# Start_Line.net
KiCad netlist of a schematic drawn in EAGLE
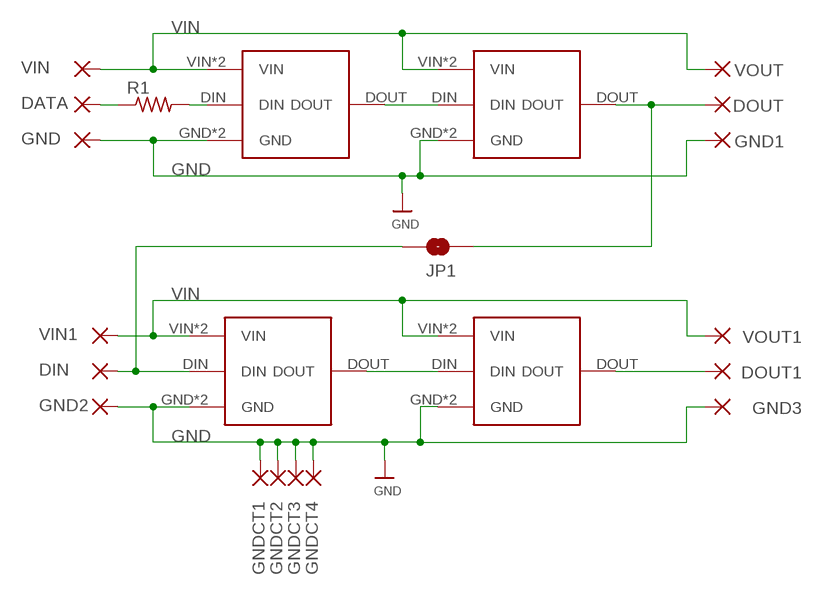
[diagram p0: schematic, sheet 1]

(export (version "E")
  (design (tool "Eeschema 10.0.6"))
  (components
    (comp (ref "DATA")
      (value "SMD5")
      (footprint "eagle-import:SMD2,54-5,08")
      (libsource (lib "eagle-import") (part "wirepad_412_SMD5"))
    )
    (comp (ref "DIN")
      (value "SMD5")
      (footprint "eagle-import:SMD2,54-5,08")
      (libsource (lib "eagle-import") (part "wirepad_412_SMD5"))
    )
    (comp (ref "DOUT")
      (value "SMD5")
      (footprint "eagle-import:SMD2,54-5,08")
      (libsource (lib "eagle-import") (part "wirepad_412_SMD5"))
    )
    (comp (ref "DOUT1")
      (value "SMD5")
      (footprint "eagle-import:SMD2,54-5,08")
      (libsource (lib "eagle-import") (part "wirepad_412_SMD5"))
    )
    (comp (ref "GND")
      (value "SMD5")
      (footprint "eagle-import:SMD2,54-5,08")
      (libsource (lib "eagle-import") (part "wirepad_412_SMD5"))
    )
    (comp (ref "GND1")
      (value "SMD5")
      (footprint "eagle-import:SMD2,54-5,08")
      (libsource (lib "eagle-import") (part "wirepad_412_SMD5"))
    )
    (comp (ref "GND2")
      (value "SMD5")
      (footprint "eagle-import:SMD2,54-5,08")
      (libsource (lib "eagle-import") (part "wirepad_412_SMD5"))
    )
    (comp (ref "GND3")
      (value "SMD5")
      (footprint "eagle-import:SMD2,54-5,08")
      (libsource (lib "eagle-import") (part "wirepad_412_SMD5"))
    )
    (comp (ref "GNDCT1")
      (value "SMD5")
      (footprint "eagle-import:SMD5,5X5")
      (libsource (lib "eagle-import") (part "SMD5"))
    )
    (comp (ref "GNDCT2")
      (value "SMD5")
      (footprint "eagle-import:SMD5,5X5")
      (libsource (lib "eagle-import") (part "SMD5"))
    )
    (comp (ref "GNDCT3")
      (value "SMD5")
      (footprint "eagle-import:SMD5,5X5")
      (libsource (lib "eagle-import") (part "SMD5"))
    )
    (comp (ref "GNDCT4")
      (value "SMD5")
      (footprint "eagle-import:SMD5,5X5")
      (libsource (lib "eagle-import") (part "SMD5"))
    )
    (comp (ref "JP1")
      (value "JUMPER-SMT_2_NO_SILK")
      (footprint "eagle-import:SMT-JUMPER_2_NO_SILK")
      (libsource (lib "eagle-import") (part "JUMPER-SMT_2_NO_SILK"))
    )
    (comp (ref "R1")
      (value "R-US_R1206")
      (footprint "eagle-import:R1206")
      (libsource (lib "eagle-import") (part "R-US_R1206"))
    )
    (comp (ref "U$1")
      (value "NP-1")
      (footprint "eagle-import:NP-1")
      (libsource (lib "eagle-import") (part "NP-1"))
    )
    (comp (ref "U$3")
      (value "NP-1")
      (footprint "eagle-import:NP-1")
      (libsource (lib "eagle-import") (part "NP-1"))
    )
    (comp (ref "U$5")
      (value "NP-3")
      (footprint "eagle-import:NP-3")
      (libsource (lib "eagle-import") (part "NP-3"))
    )
    (comp (ref "U$8")
      (value "NP-3")
      (footprint "eagle-import:NP-3")
      (libsource (lib "eagle-import") (part "NP-3"))
    )
    (comp (ref "VIN")
      (value "SMD5")
      (footprint "eagle-import:SMD2,54-5,08")
      (libsource (lib "eagle-import") (part "wirepad_412_SMD5"))
    )
    (comp (ref "VIN1")
      (value "SMD5")
      (footprint "eagle-import:SMD2,54-5,08")
      (libsource (lib "eagle-import") (part "wirepad_412_SMD5"))
    )
    (comp (ref "VOUT")
      (value "SMD5")
      (footprint "eagle-import:SMD2,54-5,08")
      (libsource (lib "eagle-import") (part "wirepad_412_SMD5"))
    )
    (comp (ref "VOUT1")
      (value "SMD5")
      (footprint "eagle-import:SMD2,54-5,08")
      (libsource (lib "eagle-import") (part "wirepad_412_SMD5"))
    )
  )
  (nets
    (net (code "1") (name "/VIN") (class "Default")
      (node (ref "U$1") (pin "VIN") (pinfunction "VIN_VIN") (pintype "bidirectional"))
      (node (ref "U$1") (pin "VOUT") (pinfunction "VIN_VOUT") (pintype "bidirectional"))
      (node (ref "U$3") (pin "VIN") (pinfunction "VIN_VIN") (pintype "bidirectional"))
      (node (ref "U$3") (pin "VOUT") (pinfunction "VIN_VOUT") (pintype "bidirectional"))
      (node (ref "U$5") (pin "VIN") (pinfunction "VIN_VIN") (pintype "bidirectional"))
      (node (ref "U$5") (pin "VOUT") (pinfunction "VIN_VOUT") (pintype "bidirectional"))
      (node (ref "U$8") (pin "VIN") (pinfunction "VIN_VIN") (pintype "bidirectional"))
      (node (ref "U$8") (pin "VOUT") (pinfunction "VIN_VOUT") (pintype "bidirectional"))
      (node (ref "VIN") (pin "1") (pinfunction "P_1") (pintype "passive"))
      (node (ref "VIN1") (pin "1") (pinfunction "P_1") (pintype "passive"))
      (node (ref "VOUT") (pin "1") (pinfunction "P_1") (pintype "passive"))
      (node (ref "VOUT1") (pin "1") (pinfunction "P_1") (pintype "passive"))
    )
    (net (code "2") (name "GND") (class "Default")
      (node (ref "GND") (pin "1") (pinfunction "P_1") (pintype "passive"))
      (node (ref "GND1") (pin "1") (pinfunction "P_1") (pintype "passive"))
      (node (ref "GND2") (pin "1") (pinfunction "P_1") (pintype "passive"))
      (node (ref "GND3") (pin "1") (pinfunction "P_1") (pintype "passive"))
      (node (ref "GNDCT1") (pin "1") (pinfunction "P_1") (pintype "passive"))
      (node (ref "GNDCT2") (pin "1") (pinfunction "P_1") (pintype "passive"))
      (node (ref "GNDCT3") (pin "1") (pinfunction "P_1") (pintype "passive"))
      (node (ref "GNDCT4") (pin "1") (pinfunction "P_1") (pintype "passive"))
      (node (ref "U$1") (pin "GND") (pinfunction "GND_GND") (pintype "bidirectional"))
      (node (ref "U$1") (pin "GND1") (pinfunction "GND_GND1") (pintype "bidirectional"))
      (node (ref "U$3") (pin "GND") (pinfunction "GND_GND") (pintype "bidirectional"))
      (node (ref "U$3") (pin "GND1") (pinfunction "GND_GND1") (pintype "bidirectional"))
      (node (ref "U$5") (pin "GND") (pinfunction "GND_GND") (pintype "bidirectional"))
      (node (ref "U$5") (pin "GND1") (pinfunction "GND_GND1") (pintype "bidirectional"))
      (node (ref "U$8") (pin "GND") (pinfunction "GND_GND") (pintype "bidirectional"))
      (node (ref "U$8") (pin "GND1") (pinfunction "GND_GND1") (pintype "bidirectional"))
    )
    (net (code "3") (name "Net-(DATA-P)") (class "Default")
      (node (ref "DATA") (pin "1") (pinfunction "P_1") (pintype "passive"))
      (node (ref "R1") (pin "1") (pinfunction "1_1") (pintype "passive"))
    )
    (net (code "4") (name "Net-(DIN-P)") (class "Default")
      (node (ref "DIN") (pin "1") (pinfunction "P_1") (pintype "passive"))
      (node (ref "JP1") (pin "2") (pinfunction "2_2") (pintype "passive"))
      (node (ref "U$1") (pin "DIN") (pinfunction "DIN_DIN") (pintype "bidirectional"))
    )
    (net (code "5") (name "Net-(DOUT-P)") (class "Default")
      (node (ref "DOUT") (pin "1") (pinfunction "P_1") (pintype "passive"))
      (node (ref "JP1") (pin "1") (pinfunction "1_1") (pintype "passive"))
      (node (ref "U$8") (pin "DOUT") (pinfunction "DOUT_DOUT") (pintype "bidirectional"))
    )
    (net (code "6") (name "Net-(DOUT1-P)") (class "Default")
      (node (ref "DOUT1") (pin "1") (pinfunction "P_1") (pintype "passive"))
      (node (ref "U$3") (pin "DOUT") (pinfunction "DOUT_DOUT") (pintype "bidirectional"))
    )
    (net (code "7") (name "Net-(R1-Pad2)") (class "Default")
      (node (ref "R1") (pin "2") (pinfunction "2_2") (pintype "passive"))
      (node (ref "U$5") (pin "DIN") (pinfunction "DIN_DIN") (pintype "bidirectional"))
    )
    (net (code "8") (name "Net-(U$1-PadDOUT)") (class "Default")
      (node (ref "U$1") (pin "DOUT") (pinfunction "DOUT_DOUT") (pintype "bidirectional"))
      (node (ref "U$3") (pin "DIN") (pinfunction "DIN_DIN") (pintype "bidirectional"))
    )
    (net (code "9") (name "Net-(U$5-PadDOUT)") (class "Default")
      (node (ref "U$5") (pin "DOUT") (pinfunction "DOUT_DOUT") (pintype "bidirectional"))
      (node (ref "U$8") (pin "DIN") (pinfunction "DIN_DIN") (pintype "bidirectional"))
    )
  )
)
